# SCH_graduation_atmega_2023-07-09.net
KiCad netlist of a schematic drawn in EasyEDA
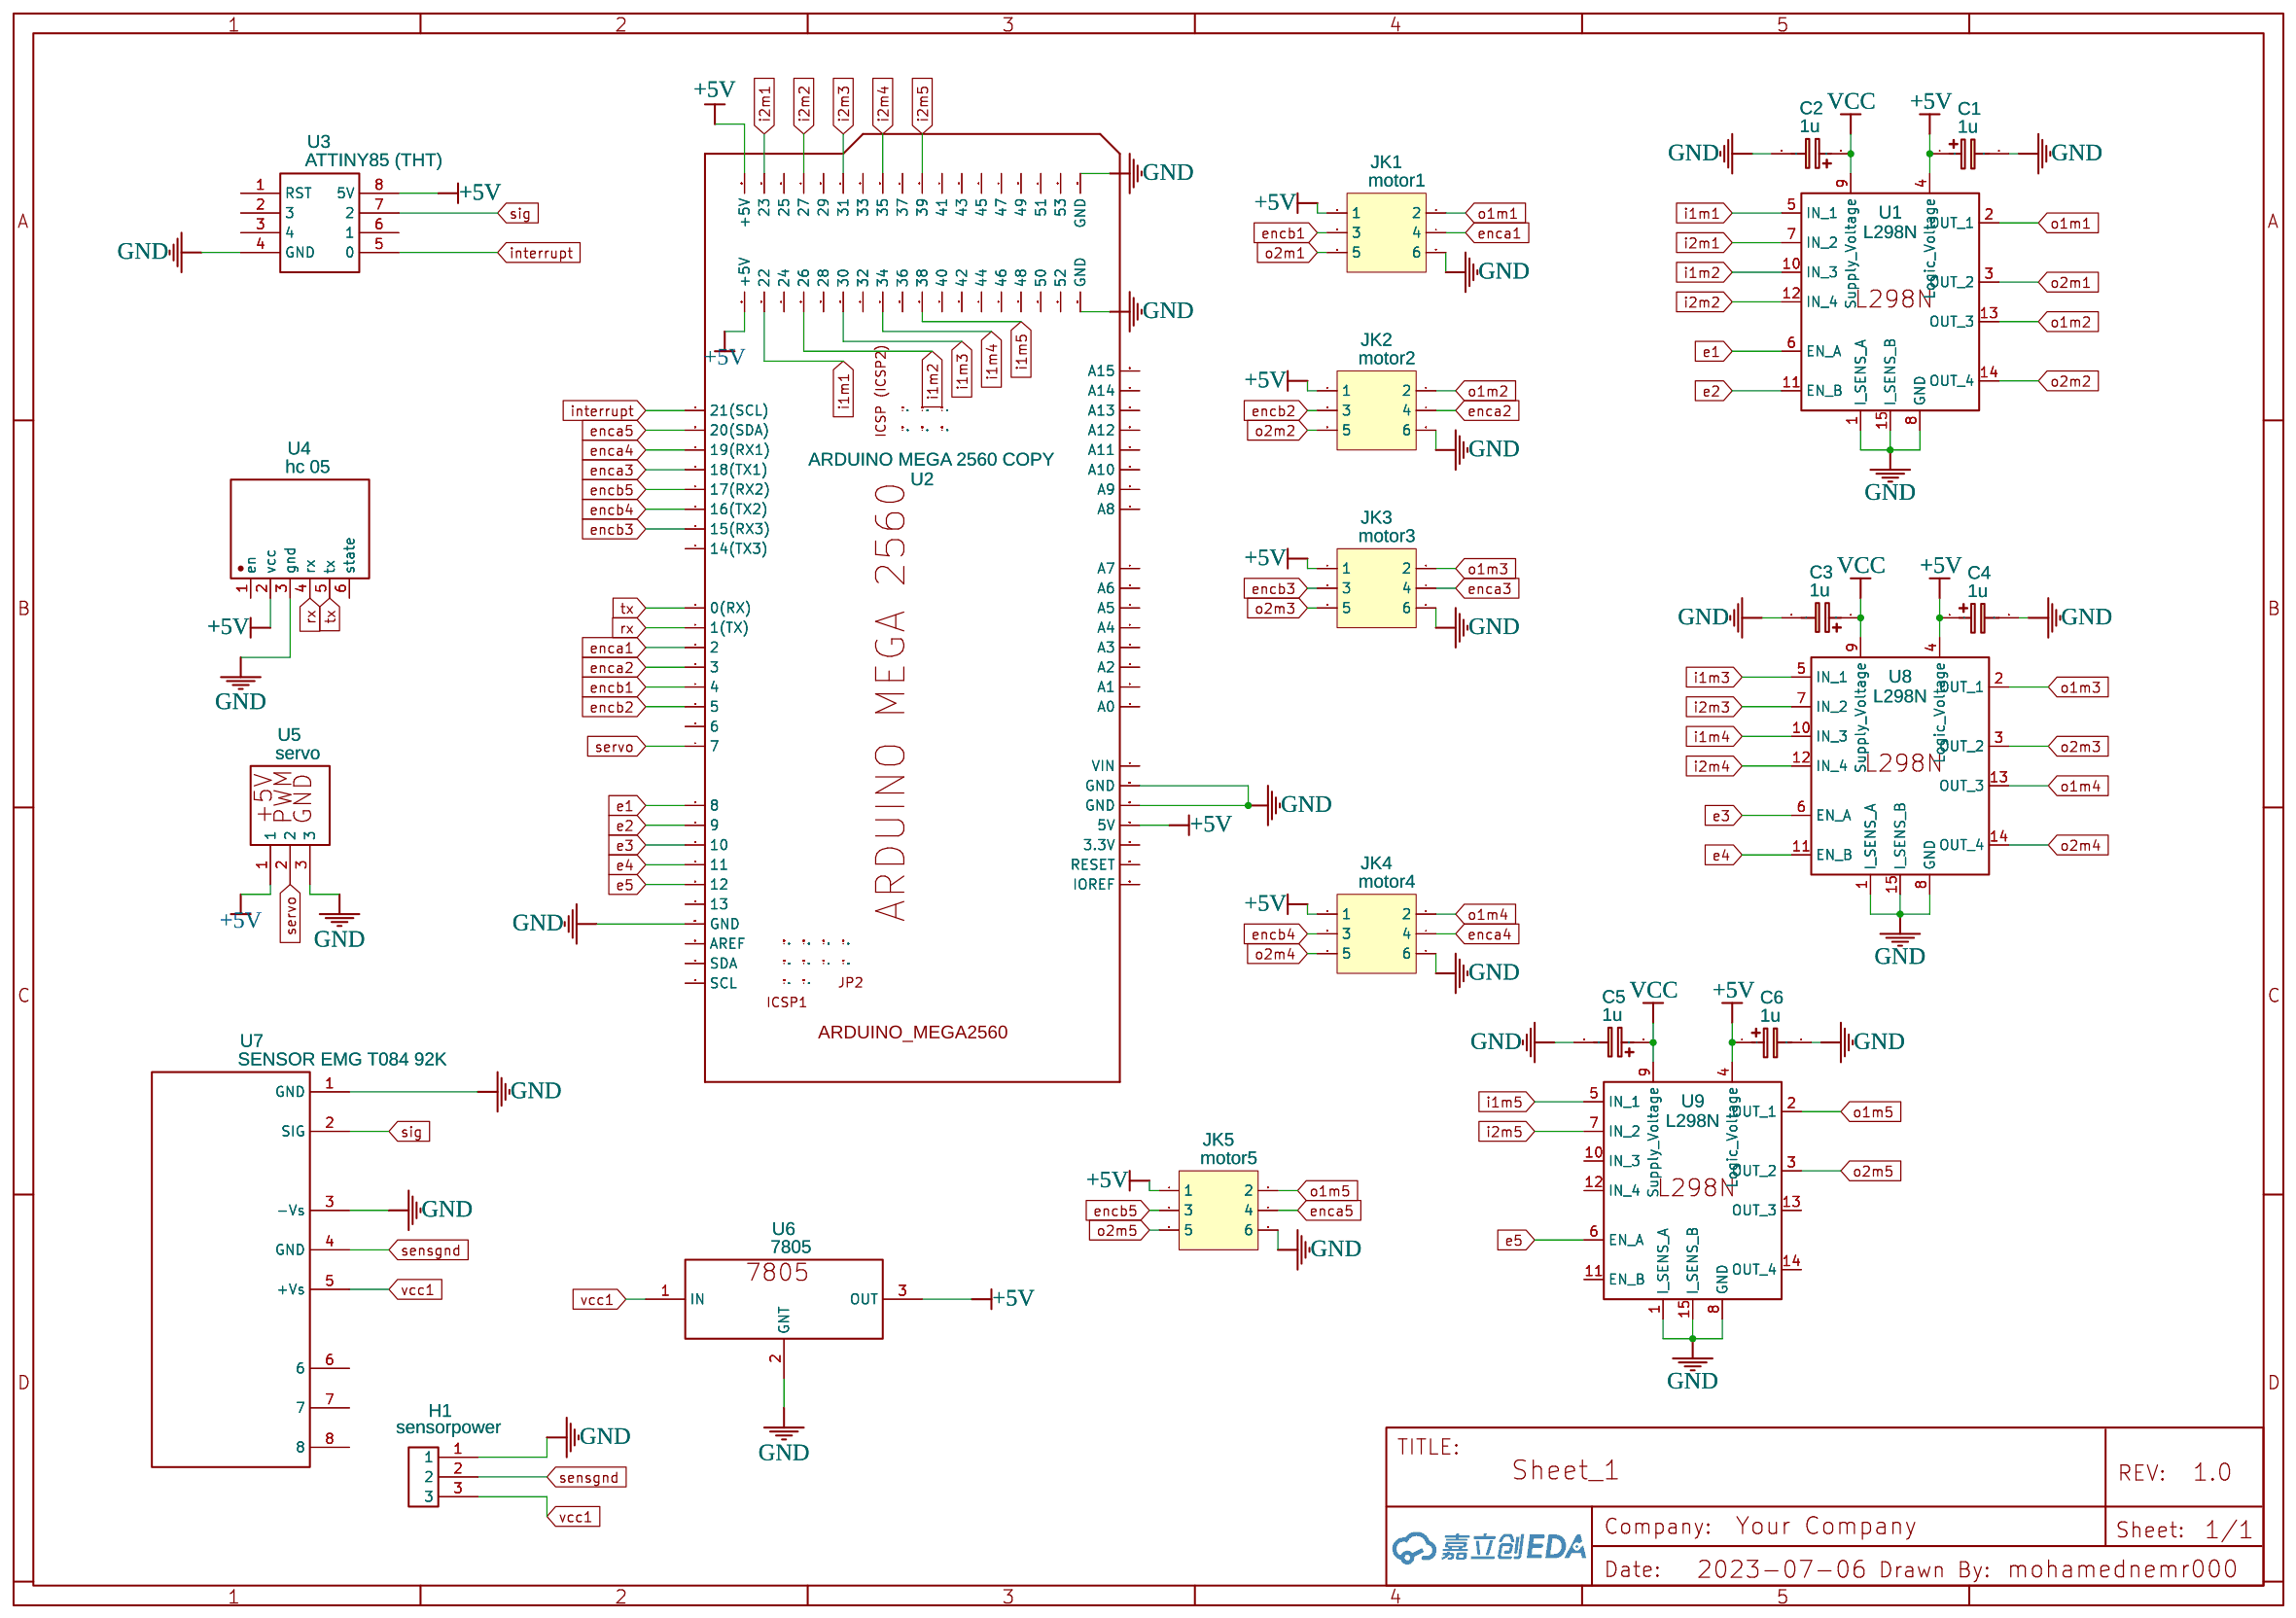
[diagram p0: schematic sheet]

(export (version "E")
  (design (tool "Eeschema 10.0.6"))
  (components
    (comp (ref "C1") (value "1u") (libsource (lib "") (part "CE_TH_D3.0×F1.5_EU_2")))
    (comp (ref "C2") (value "1u") (libsource (lib "") (part "CE_TH_D3.0×F1.5_EU_3")))
    (comp (ref "C3") (value "1u") (libsource (lib "") (part "CE_TH_D3.0×F1.5_EU_1")))
    (comp (ref "C4") (value "1u") (libsource (lib "") (part "CE_TH_D3.0×F1.5_EU")))
    (comp (ref "C5") (value "1u") (libsource (lib "") (part "CE_TH_D3.0×F1.5_EU_1")))
    (comp (ref "C6") (value "1u") (libsource (lib "") (part "CE_TH_D3.0×F1.5_EU")))
    (comp (ref "H1") (value "sensorpower") (libsource (lib "") (part "Header_3*1")))
    (comp (ref "JK1") (value "motor1") (libsource (lib "") (part "CON3*2")))
    (comp (ref "JK2") (value "motor2") (libsource (lib "") (part "CON3*2")))
    (comp (ref "JK3") (value "motor3") (libsource (lib "") (part "CON3*2")))
    (comp (ref "JK4") (value "motor4") (libsource (lib "") (part "CON3*2")))
    (comp (ref "JK5") (value "motor5") (libsource (lib "") (part "CON3*2")))
    (comp (ref "U1") (value "L298N") (libsource (lib "") (part "L298N")))
    (comp (ref "U2") (value "ARDUINO MEGA 2560 COPY") (libsource (lib "") (part "ARDUINO MEGA 2560 COPY")))
    (comp (ref "U3")
      (value "ATTINY85 (THT)")
      (fields
        (field (name "BOM_Manufacturer Part") "ATTINY85-20PU")
        (field (name "BOM_Supplier Part") "1455162")
      )
      (libsource (lib "") (part "ATTINY85 (THT)"))
    )
    (comp (ref "U4") (value "hc 05") (libsource (lib "") (part "hc 05")))
    (comp (ref "U5") (value "servo") (libsource (lib "") (part "servo")))
    (comp (ref "U6") (value "7805") (libsource (lib "") (part "7805")))
    (comp (ref "U7") (value "SENSOR EMG T084 92K") (libsource (lib "") (part "SENSOR EMG T084 92K")))
    (comp (ref "U8") (value "L298N") (libsource (lib "") (part "L298N")))
    (comp (ref "U9") (value "L298N") (libsource (lib "") (part "L298N")))
  )
  (nets
    (net (code "1") (name "+5V") (class "Default")
      (node (ref "C1") (pin "1") (pinfunction "1_1") (pintype "unspecified"))
      (node (ref "C4") (pin "1") (pinfunction "1_1") (pintype "unspecified"))
      (node (ref "C6") (pin "1") (pinfunction "1_1") (pintype "unspecified"))
      (node (ref "JK1") (pin "1") (pinfunction "1_1") (pintype "unspecified"))
      (node (ref "JK2") (pin "1") (pinfunction "1_1") (pintype "unspecified"))
      (node (ref "JK3") (pin "1") (pinfunction "1_1") (pintype "unspecified"))
      (node (ref "JK4") (pin "1") (pinfunction "1_1") (pintype "unspecified"))
      (node (ref "JK5") (pin "1") (pinfunction "1_1") (pintype "unspecified"))
      (node (ref "U1") (pin "4") (pinfunction "Logic_Voltage_4") (pintype "unspecified"))
      (node (ref "U2") (pin "5V_1") (pinfunction "+5V_5V_1") (pintype "unspecified"))
      (node (ref "U2") (pin "5V_2") (pinfunction "+5V_5V_2") (pintype "unspecified"))
      (node (ref "U2") (pin "5V_3") (pinfunction "5V_5V_3") (pintype "unspecified"))
      (node (ref "U3") (pin "8") (pinfunction "5V_8") (pintype "unspecified"))
      (node (ref "U4") (pin "2") (pinfunction "vcc_2") (pintype "unspecified"))
      (node (ref "U5") (pin "1") (pinfunction "1_1") (pintype "unspecified"))
      (node (ref "U6") (pin "3") (pinfunction "OUT_3") (pintype "unspecified"))
      (node (ref "U8") (pin "4") (pinfunction "Logic_Voltage_4") (pintype "unspecified"))
      (node (ref "U9") (pin "4") (pinfunction "Logic_Voltage_4") (pintype "unspecified"))
    )
    (net (code "2") (name "GND") (class "Default")
      (node (ref "C1") (pin "2") (pinfunction "2_2") (pintype "unspecified"))
      (node (ref "C2") (pin "2") (pinfunction "2_2") (pintype "unspecified"))
      (node (ref "C3") (pin "2") (pinfunction "2_2") (pintype "unspecified"))
      (node (ref "C4") (pin "2") (pinfunction "2_2") (pintype "unspecified"))
      (node (ref "C5") (pin "2") (pinfunction "2_2") (pintype "unspecified"))
      (node (ref "C6") (pin "2") (pinfunction "2_2") (pintype "unspecified"))
      (node (ref "H1") (pin "1") (pinfunction "1_1") (pintype "unspecified"))
      (node (ref "JK1") (pin "6") (pinfunction "6_6") (pintype "unspecified"))
      (node (ref "JK2") (pin "6") (pinfunction "6_6") (pintype "unspecified"))
      (node (ref "JK3") (pin "6") (pinfunction "6_6") (pintype "unspecified"))
      (node (ref "JK4") (pin "6") (pinfunction "6_6") (pintype "unspecified"))
      (node (ref "JK5") (pin "6") (pinfunction "6_6") (pintype "unspecified"))
      (node (ref "U1") (pin "1") (pinfunction "I_SENS_A_1") (pintype "unspecified"))
      (node (ref "U1") (pin "15") (pinfunction "I_SENS_B_15") (pintype "unspecified"))
      (node (ref "U1") (pin "8") (pinfunction "GND_8") (pintype "unspecified"))
      (node (ref "U2") (pin "GND_1") (pinfunction "GND_GND_1") (pintype "unspecified"))
      (node (ref "U2") (pin "GND_2") (pinfunction "GND_GND_2") (pintype "unspecified"))
      (node (ref "U2") (pin "GND_3") (pinfunction "GND_GND_3") (pintype "unspecified"))
      (node (ref "U2") (pin "GND_4") (pinfunction "GND_GND_4") (pintype "unspecified"))
      (node (ref "U2") (pin "GND_5") (pinfunction "GND_GND_5") (pintype "unspecified"))
      (node (ref "U3") (pin "4") (pinfunction "GND_4") (pintype "unspecified"))
      (node (ref "U4") (pin "3") (pinfunction "gnd_3") (pintype "unspecified"))
      (node (ref "U5") (pin "3") (pinfunction "3_3") (pintype "unspecified"))
      (node (ref "U6") (pin "2") (pinfunction "GNT_2") (pintype "unspecified"))
      (node (ref "U7") (pin "1") (pinfunction "GND_1") (pintype "unspecified"))
      (node (ref "U7") (pin "3") (pinfunction "-Vs_3") (pintype "unspecified"))
      (node (ref "U8") (pin "1") (pinfunction "I_SENS_A_1") (pintype "unspecified"))
      (node (ref "U8") (pin "15") (pinfunction "I_SENS_B_15") (pintype "unspecified"))
      (node (ref "U8") (pin "8") (pinfunction "GND_8") (pintype "unspecified"))
      (node (ref "U9") (pin "1") (pinfunction "I_SENS_A_1") (pintype "unspecified"))
      (node (ref "U9") (pin "15") (pinfunction "I_SENS_B_15") (pintype "unspecified"))
      (node (ref "U9") (pin "8") (pinfunction "GND_8") (pintype "unspecified"))
    )
    (net (code "3") (name "VCC") (class "Default")
      (node (ref "C2") (pin "1") (pinfunction "1_1") (pintype "unspecified"))
      (node (ref "C3") (pin "1") (pinfunction "1_1") (pintype "unspecified"))
      (node (ref "C5") (pin "1") (pinfunction "1_1") (pintype "unspecified"))
      (node (ref "U1") (pin "9") (pinfunction "Supply_Voltage_9") (pintype "unspecified"))
      (node (ref "U8") (pin "9") (pinfunction "Supply_Voltage_9") (pintype "unspecified"))
      (node (ref "U9") (pin "9") (pinfunction "Supply_Voltage_9") (pintype "unspecified"))
    )
    (net (code "4") (name "e1") (class "Default")
      (node (ref "U1") (pin "6") (pinfunction "EN_A_6") (pintype "unspecified"))
      (node (ref "U2") (pin "8") (pinfunction "8_8") (pintype "unspecified"))
    )
    (net (code "5") (name "e2") (class "Default")
      (node (ref "U1") (pin "11") (pinfunction "EN_B_11") (pintype "unspecified"))
      (node (ref "U2") (pin "9") (pinfunction "9_9") (pintype "unspecified"))
    )
    (net (code "6") (name "e3") (class "Default")
      (node (ref "U2") (pin "10") (pinfunction "10_10") (pintype "unspecified"))
      (node (ref "U8") (pin "6") (pinfunction "EN_A_6") (pintype "unspecified"))
    )
    (net (code "7") (name "e4") (class "Default")
      (node (ref "U2") (pin "11") (pinfunction "11_11") (pintype "unspecified"))
      (node (ref "U8") (pin "11") (pinfunction "EN_B_11") (pintype "unspecified"))
    )
    (net (code "8") (name "e5") (class "Default")
      (node (ref "U2") (pin "12") (pinfunction "12_12") (pintype "unspecified"))
      (node (ref "U9") (pin "6") (pinfunction "EN_A_6") (pintype "unspecified"))
    )
    (net (code "9") (name "enca1") (class "Default")
      (node (ref "JK1") (pin "4") (pinfunction "4_4") (pintype "unspecified"))
      (node (ref "U2") (pin "2") (pinfunction "2_2") (pintype "unspecified"))
    )
    (net (code "10") (name "enca2") (class "Default")
      (node (ref "JK2") (pin "4") (pinfunction "4_4") (pintype "unspecified"))
      (node (ref "U2") (pin "3") (pinfunction "3_3") (pintype "unspecified"))
    )
    (net (code "11") (name "enca3") (class "Default")
      (node (ref "JK3") (pin "4") (pinfunction "4_4") (pintype "unspecified"))
      (node (ref "U2") (pin "18") (pinfunction "18(TX1)_18") (pintype "unspecified"))
    )
    (net (code "12") (name "enca4") (class "Default")
      (node (ref "JK4") (pin "4") (pinfunction "4_4") (pintype "unspecified"))
      (node (ref "U2") (pin "19") (pinfunction "19(RX1)_19") (pintype "unspecified"))
    )
    (net (code "13") (name "enca5") (class "Default")
      (node (ref "JK5") (pin "4") (pinfunction "4_4") (pintype "unspecified"))
      (node (ref "U2") (pin "20") (pinfunction "20(SDA)_20") (pintype "unspecified"))
    )
    (net (code "14") (name "encb1") (class "Default")
      (node (ref "JK1") (pin "3") (pinfunction "3_3") (pintype "unspecified"))
      (node (ref "U2") (pin "4") (pinfunction "4_4") (pintype "unspecified"))
    )
    (net (code "15") (name "encb2") (class "Default")
      (node (ref "JK2") (pin "3") (pinfunction "3_3") (pintype "unspecified"))
      (node (ref "U2") (pin "5") (pinfunction "5_5") (pintype "unspecified"))
    )
    (net (code "16") (name "encb3") (class "Default")
      (node (ref "JK3") (pin "3") (pinfunction "3_3") (pintype "unspecified"))
      (node (ref "U2") (pin "15") (pinfunction "15(RX3)_15") (pintype "unspecified"))
    )
    (net (code "17") (name "encb4") (class "Default")
      (node (ref "JK4") (pin "3") (pinfunction "3_3") (pintype "unspecified"))
      (node (ref "U2") (pin "16") (pinfunction "16(TX2)_16") (pintype "unspecified"))
    )
    (net (code "18") (name "encb5") (class "Default")
      (node (ref "JK5") (pin "3") (pinfunction "3_3") (pintype "unspecified"))
      (node (ref "U2") (pin "17") (pinfunction "17(RX2)_17") (pintype "unspecified"))
    )
    (net (code "19") (name "i1m1") (class "Default")
      (node (ref "U1") (pin "5") (pinfunction "IN_1_5") (pintype "unspecified"))
      (node (ref "U2") (pin "22") (pinfunction "22_22") (pintype "unspecified"))
    )
    (net (code "20") (name "i1m2") (class "Default")
      (node (ref "U1") (pin "10") (pinfunction "IN_3_10") (pintype "unspecified"))
      (node (ref "U2") (pin "26") (pinfunction "26_26") (pintype "unspecified"))
    )
    (net (code "21") (name "i1m3") (class "Default")
      (node (ref "U2") (pin "30") (pinfunction "30_30") (pintype "unspecified"))
      (node (ref "U8") (pin "5") (pinfunction "IN_1_5") (pintype "unspecified"))
    )
    (net (code "22") (name "i1m4") (class "Default")
      (node (ref "U2") (pin "34") (pinfunction "34_34") (pintype "unspecified"))
      (node (ref "U8") (pin "10") (pinfunction "IN_3_10") (pintype "unspecified"))
    )
    (net (code "23") (name "i1m5") (class "Default")
      (node (ref "U2") (pin "38") (pinfunction "38_38") (pintype "unspecified"))
      (node (ref "U9") (pin "5") (pinfunction "IN_1_5") (pintype "unspecified"))
    )
    (net (code "24") (name "i2m1") (class "Default")
      (node (ref "U1") (pin "7") (pinfunction "IN_2_7") (pintype "unspecified"))
      (node (ref "U2") (pin "23") (pinfunction "23_23") (pintype "unspecified"))
    )
    (net (code "25") (name "i2m2") (class "Default")
      (node (ref "U1") (pin "12") (pinfunction "IN_4_12") (pintype "unspecified"))
      (node (ref "U2") (pin "27") (pinfunction "27_27") (pintype "unspecified"))
    )
    (net (code "26") (name "i2m3") (class "Default")
      (node (ref "U2") (pin "31") (pinfunction "31_31") (pintype "unspecified"))
      (node (ref "U8") (pin "7") (pinfunction "IN_2_7") (pintype "unspecified"))
    )
    (net (code "27") (name "i2m4") (class "Default")
      (node (ref "U2") (pin "35") (pinfunction "35_35") (pintype "unspecified"))
      (node (ref "U8") (pin "12") (pinfunction "IN_4_12") (pintype "unspecified"))
    )
    (net (code "28") (name "i2m5") (class "Default")
      (node (ref "U2") (pin "39") (pinfunction "39_39") (pintype "unspecified"))
      (node (ref "U9") (pin "7") (pinfunction "IN_2_7") (pintype "unspecified"))
    )
    (net (code "29") (name "interrupt") (class "Default")
      (node (ref "U2") (pin "21") (pinfunction "21(SCL)_21") (pintype "unspecified"))
      (node (ref "U3") (pin "5") (pinfunction "0_5") (pintype "unspecified"))
    )
    (net (code "30") (name "o1m1") (class "Default")
      (node (ref "JK1") (pin "2") (pinfunction "2_2") (pintype "unspecified"))
      (node (ref "U1") (pin "2") (pinfunction "OUT_1_2") (pintype "unspecified"))
    )
    (net (code "31") (name "o1m2") (class "Default")
      (node (ref "JK2") (pin "2") (pinfunction "2_2") (pintype "unspecified"))
      (node (ref "U1") (pin "13") (pinfunction "OUT_3_13") (pintype "unspecified"))
    )
    (net (code "32") (name "o1m3") (class "Default")
      (node (ref "JK3") (pin "2") (pinfunction "2_2") (pintype "unspecified"))
      (node (ref "U8") (pin "2") (pinfunction "OUT_1_2") (pintype "unspecified"))
    )
    (net (code "33") (name "o1m4") (class "Default")
      (node (ref "JK4") (pin "2") (pinfunction "2_2") (pintype "unspecified"))
      (node (ref "U8") (pin "13") (pinfunction "OUT_3_13") (pintype "unspecified"))
    )
    (net (code "34") (name "o1m5") (class "Default")
      (node (ref "JK5") (pin "2") (pinfunction "2_2") (pintype "unspecified"))
      (node (ref "U9") (pin "2") (pinfunction "OUT_1_2") (pintype "unspecified"))
    )
    (net (code "35") (name "o2m1") (class "Default")
      (node (ref "JK1") (pin "5") (pinfunction "5_5") (pintype "unspecified"))
      (node (ref "U1") (pin "3") (pinfunction "OUT_2_3") (pintype "unspecified"))
    )
    (net (code "36") (name "o2m2") (class "Default")
      (node (ref "JK2") (pin "5") (pinfunction "5_5") (pintype "unspecified"))
      (node (ref "U1") (pin "14") (pinfunction "OUT_4_14") (pintype "unspecified"))
    )
    (net (code "37") (name "o2m3") (class "Default")
      (node (ref "JK3") (pin "5") (pinfunction "5_5") (pintype "unspecified"))
      (node (ref "U8") (pin "3") (pinfunction "OUT_2_3") (pintype "unspecified"))
    )
    (net (code "38") (name "o2m4") (class "Default")
      (node (ref "JK4") (pin "5") (pinfunction "5_5") (pintype "unspecified"))
      (node (ref "U8") (pin "14") (pinfunction "OUT_4_14") (pintype "unspecified"))
    )
    (net (code "39") (name "o2m5") (class "Default")
      (node (ref "JK5") (pin "5") (pinfunction "5_5") (pintype "unspecified"))
      (node (ref "U9") (pin "3") (pinfunction "OUT_2_3") (pintype "unspecified"))
    )
    (net (code "40") (name "rx") (class "Default")
      (node (ref "U2") (pin "1") (pinfunction "1(TX)_1") (pintype "unspecified"))
      (node (ref "U4") (pin "4") (pinfunction "rx_4") (pintype "unspecified"))
    )
    (net (code "41") (name "sensgnd") (class "Default")
      (node (ref "H1") (pin "2") (pinfunction "2_2") (pintype "unspecified"))
      (node (ref "U7") (pin "4") (pinfunction "GND_4") (pintype "unspecified"))
    )
    (net (code "42") (name "servo") (class "Default")
      (node (ref "U2") (pin "7") (pinfunction "7_7") (pintype "unspecified"))
      (node (ref "U5") (pin "2") (pinfunction "2_2") (pintype "unspecified"))
    )
    (net (code "43") (name "sig") (class "Default")
      (node (ref "U3") (pin "7") (pinfunction "2_7") (pintype "unspecified"))
      (node (ref "U7") (pin "2") (pinfunction "SIG_2") (pintype "unspecified"))
    )
    (net (code "44") (name "tx") (class "Default")
      (node (ref "U2") (pin "0") (pinfunction "0(RX)_0") (pintype "unspecified"))
      (node (ref "U4") (pin "5") (pinfunction "tx_5") (pintype "unspecified"))
    )
    (net (code "45") (name "unconnected-(U2-+5V_-PadICSP1_5)") (class "Default")
      (node (ref "U2") (pin "ICSP1_5") (pinfunction "+5V__ICSP1_5") (pintype "unspecified"))
    )
    (net (code "46") (name "unconnected-(U2-+5V_-PadICSP2_2)") (class "Default")
      (node (ref "U2") (pin "ICSP2_2") (pinfunction "+5V__ICSP2_2") (pintype "unspecified"))
    )
    (net (code "47") (name "unconnected-(U2-3.3V-Pad3V3)") (class "Default")
      (node (ref "U2") (pin "3V3") (pinfunction "3.3V_3V3") (pintype "unspecified"))
    )
    (net (code "48") (name "unconnected-(U2-14(TX3)-Pad14)") (class "Default")
      (node (ref "U2") (pin "14") (pinfunction "14(TX3)_14") (pintype "unspecified"))
    )
    (net (code "49") (name "unconnected-(U2-GND_-PadICSP1_1)") (class "Default")
      (node (ref "U2") (pin "ICSP1_1") (pinfunction "GND__ICSP1_1") (pintype "unspecified"))
    )
    (net (code "50") (name "unconnected-(U2-GND_-PadICSP2_6)") (class "Default")
      (node (ref "U2") (pin "ICSP2_6") (pinfunction "GND__ICSP2_6") (pintype "unspecified"))
    )
    (net (code "51") (name "unconnected-(U2-GND_-PadJP2_1)") (class "Default")
      (node (ref "U2") (pin "JP2_1") (pinfunction "GND__JP2_1") (pintype "unspecified"))
    )
    (net (code "52") (name "unconnected-(U2-MISO-PadICSP1_6)") (class "Default")
      (node (ref "U2") (pin "ICSP1_6") (pinfunction "MISO_ICSP1_6") (pintype "unspecified"))
    )
    (net (code "53") (name "unconnected-(U2-MISO-PadICSP2_1)") (class "Default")
      (node (ref "U2") (pin "ICSP2_1") (pinfunction "MISO_ICSP2_1") (pintype "unspecified"))
    )
    (net (code "54") (name "unconnected-(U2-MOSI-PadICSP1_3)") (class "Default")
      (node (ref "U2") (pin "ICSP1_3") (pinfunction "MOSI_ICSP1_3") (pintype "unspecified"))
    )
    (net (code "55") (name "unconnected-(U2-MOSI-PadICSP2_4)") (class "Default")
      (node (ref "U2") (pin "ICSP2_4") (pinfunction "MOSI_ICSP2_4") (pintype "unspecified"))
    )
    (net (code "56") (name "unconnected-(U2-MOSI-PadJP2_3)") (class "Default")
      (node (ref "U2") (pin "JP2_3") (pinfunction "MOSI_JP2_3") (pintype "unspecified"))
    )
    (net (code "57") (name "unconnected-(U2-Pad6)") (class "Default")
      (node (ref "U2") (pin "6") (pinfunction "6_6") (pintype "unspecified"))
    )
    (net (code "58") (name "unconnected-(U2-Pad13)") (class "Default")
      (node (ref "U2") (pin "13") (pinfunction "13_13") (pintype "unspecified"))
    )
    (net (code "59") (name "unconnected-(U2-Pad24)") (class "Default")
      (node (ref "U2") (pin "24") (pinfunction "24_24") (pintype "unspecified"))
    )
    (net (code "60") (name "unconnected-(U2-Pad25)") (class "Default")
      (node (ref "U2") (pin "25") (pinfunction "25_25") (pintype "unspecified"))
    )
    (net (code "61") (name "unconnected-(U2-Pad28)") (class "Default")
      (node (ref "U2") (pin "28") (pinfunction "28_28") (pintype "unspecified"))
    )
    (net (code "62") (name "unconnected-(U2-Pad29)") (class "Default")
      (node (ref "U2") (pin "29") (pinfunction "29_29") (pintype "unspecified"))
    )
    (net (code "63") (name "unconnected-(U2-Pad32)") (class "Default")
      (node (ref "U2") (pin "32") (pinfunction "32_32") (pintype "unspecified"))
    )
    (net (code "64") (name "unconnected-(U2-Pad33)") (class "Default")
      (node (ref "U2") (pin "33") (pinfunction "33_33") (pintype "unspecified"))
    )
    (net (code "65") (name "unconnected-(U2-Pad36)") (class "Default")
      (node (ref "U2") (pin "36") (pinfunction "36_36") (pintype "unspecified"))
    )
    (net (code "66") (name "unconnected-(U2-Pad37)") (class "Default")
      (node (ref "U2") (pin "37") (pinfunction "37_37") (pintype "unspecified"))
    )
    (net (code "67") (name "unconnected-(U2-Pad40)") (class "Default")
      (node (ref "U2") (pin "40") (pinfunction "40_40") (pintype "unspecified"))
    )
    (net (code "68") (name "unconnected-(U2-Pad41)") (class "Default")
      (node (ref "U2") (pin "41") (pinfunction "41_41") (pintype "unspecified"))
    )
    (net (code "69") (name "unconnected-(U2-Pad42)") (class "Default")
      (node (ref "U2") (pin "42") (pinfunction "42_42") (pintype "unspecified"))
    )
    (net (code "70") (name "unconnected-(U2-Pad43)") (class "Default")
      (node (ref "U2") (pin "43") (pinfunction "43_43") (pintype "unspecified"))
    )
    (net (code "71") (name "unconnected-(U2-Pad44)") (class "Default")
      (node (ref "U2") (pin "44") (pinfunction "44_44") (pintype "unspecified"))
    )
    (net (code "72") (name "unconnected-(U2-Pad45)") (class "Default")
      (node (ref "U2") (pin "45") (pinfunction "45_45") (pintype "unspecified"))
    )
    (net (code "73") (name "unconnected-(U2-Pad46)") (class "Default")
      (node (ref "U2") (pin "46") (pinfunction "46_46") (pintype "unspecified"))
    )
    (net (code "74") (name "unconnected-(U2-Pad47)") (class "Default")
      (node (ref "U2") (pin "47") (pinfunction "47_47") (pintype "unspecified"))
    )
    (net (code "75") (name "unconnected-(U2-Pad48)") (class "Default")
      (node (ref "U2") (pin "48") (pinfunction "48_48") (pintype "unspecified"))
    )
    (net (code "76") (name "unconnected-(U2-Pad49)") (class "Default")
      (node (ref "U2") (pin "49") (pinfunction "49_49") (pintype "unspecified"))
    )
    (net (code "77") (name "unconnected-(U2-Pad50)") (class "Default")
      (node (ref "U2") (pin "50") (pinfunction "50_50") (pintype "unspecified"))
    )
    (net (code "78") (name "unconnected-(U2-Pad51)") (class "Default")
      (node (ref "U2") (pin "51") (pinfunction "51_51") (pintype "unspecified"))
    )
    (net (code "79") (name "unconnected-(U2-Pad52)") (class "Default")
      (node (ref "U2") (pin "52") (pinfunction "52_52") (pintype "unspecified"))
    )
    (net (code "80") (name "unconnected-(U2-Pad53)") (class "Default")
      (node (ref "U2") (pin "53") (pinfunction "53_53") (pintype "unspecified"))
    )
    (net (code "81") (name "unconnected-(U2-PadA0)") (class "Default")
      (node (ref "U2") (pin "A0") (pinfunction "A0_A0") (pintype "unspecified"))
    )
    (net (code "82") (name "unconnected-(U2-PadA1)") (class "Default")
      (node (ref "U2") (pin "A1") (pinfunction "A1_A1") (pintype "unspecified"))
    )
    (net (code "83") (name "unconnected-(U2-PadA2)") (class "Default")
      (node (ref "U2") (pin "A2") (pinfunction "A2_A2") (pintype "unspecified"))
    )
    (net (code "84") (name "unconnected-(U2-PadA3)") (class "Default")
      (node (ref "U2") (pin "A3") (pinfunction "A3_A3") (pintype "unspecified"))
    )
    (net (code "85") (name "unconnected-(U2-PadA4)") (class "Default")
      (node (ref "U2") (pin "A4") (pinfunction "A4_A4") (pintype "unspecified"))
    )
    (net (code "86") (name "unconnected-(U2-PadA5)") (class "Default")
      (node (ref "U2") (pin "A5") (pinfunction "A5_A5") (pintype "unspecified"))
    )
    (net (code "87") (name "unconnected-(U2-PadA6)") (class "Default")
      (node (ref "U2") (pin "A6") (pinfunction "A6_A6") (pintype "unspecified"))
    )
    (net (code "88") (name "unconnected-(U2-PadA7)") (class "Default")
      (node (ref "U2") (pin "A7") (pinfunction "A7_A7") (pintype "unspecified"))
    )
    (net (code "89") (name "unconnected-(U2-PadA8)") (class "Default")
      (node (ref "U2") (pin "A8") (pinfunction "A8_A8") (pintype "unspecified"))
    )
    (net (code "90") (name "unconnected-(U2-PadA9)") (class "Default")
      (node (ref "U2") (pin "A9") (pinfunction "A9_A9") (pintype "unspecified"))
    )
    (net (code "91") (name "unconnected-(U2-PadA10)") (class "Default")
      (node (ref "U2") (pin "A10") (pinfunction "A10_A10") (pintype "unspecified"))
    )
    (net (code "92") (name "unconnected-(U2-PadA11)") (class "Default")
      (node (ref "U2") (pin "A11") (pinfunction "A11_A11") (pintype "unspecified"))
    )
    (net (code "93") (name "unconnected-(U2-PadA12)") (class "Default")
      (node (ref "U2") (pin "A12") (pinfunction "A12_A12") (pintype "unspecified"))
    )
    (net (code "94") (name "unconnected-(U2-PadA13)") (class "Default")
      (node (ref "U2") (pin "A13") (pinfunction "A13_A13") (pintype "unspecified"))
    )
    (net (code "95") (name "unconnected-(U2-PadA14)") (class "Default")
      (node (ref "U2") (pin "A14") (pinfunction "A14_A14") (pintype "unspecified"))
    )
    (net (code "96") (name "unconnected-(U2-PadA15)") (class "Default")
      (node (ref "U2") (pin "A15") (pinfunction "A15_A15") (pintype "unspecified"))
    )
    (net (code "97") (name "unconnected-(U2-PadAREF)") (class "Default")
      (node (ref "U2") (pin "AREF") (pinfunction "AREF_AREF") (pintype "unspecified"))
    )
    (net (code "98") (name "unconnected-(U2-PadIOREF)") (class "Default")
      (node (ref "U2") (pin "IOREF") (pinfunction "IOREF_IOREF") (pintype "unspecified"))
    )
    (net (code "99") (name "unconnected-(U2-PadRESET)") (class "Default")
      (node (ref "U2") (pin "RESET") (pinfunction "RESET_RESET") (pintype "unspecified"))
    )
    (net (code "100") (name "unconnected-(U2-PadSCL)") (class "Default")
      (node (ref "U2") (pin "SCL") (pinfunction "SCL_SCL") (pintype "unspecified"))
    )
    (net (code "101") (name "unconnected-(U2-PadSDA)") (class "Default")
      (node (ref "U2") (pin "SDA") (pinfunction "SDA_SDA") (pintype "unspecified"))
    )
    (net (code "102") (name "unconnected-(U2-PadVIN)") (class "Default")
      (node (ref "U2") (pin "VIN") (pinfunction "VIN_VIN") (pintype "unspecified"))
    )
    (net (code "103") (name "unconnected-(U2-RESET_-PadICSP1_2)") (class "Default")
      (node (ref "U2") (pin "ICSP1_2") (pinfunction "RESET__ICSP1_2") (pintype "unspecified"))
    )
    (net (code "104") (name "unconnected-(U2-RESET_-PadICSP2_5)") (class "Default")
      (node (ref "U2") (pin "ICSP2_5") (pinfunction "RESET__ICSP2_5") (pintype "unspecified"))
    )
    (net (code "105") (name "unconnected-(U2-RESET_-PadJP2_2)") (class "Default")
      (node (ref "U2") (pin "JP2_2") (pinfunction "RESET__JP2_2") (pintype "unspecified"))
    )
    (net (code "106") (name "unconnected-(U2-SCK-PadICSP1_4)") (class "Default")
      (node (ref "U2") (pin "ICSP1_4") (pinfunction "SCK_ICSP1_4") (pintype "unspecified"))
    )
    (net (code "107") (name "unconnected-(U2-SCK-PadICSP2_3)") (class "Default")
      (node (ref "U2") (pin "ICSP2_3") (pinfunction "SCK_ICSP2_3") (pintype "unspecified"))
    )
    (net (code "108") (name "unconnected-(U2-SCK-PadJP2_4)") (class "Default")
      (node (ref "U2") (pin "JP2_4") (pinfunction "SCK_JP2_4") (pintype "unspecified"))
    )
    (net (code "109") (name "unconnected-(U3-1-Pad6)") (class "Default")
      (node (ref "U3") (pin "6") (pinfunction "1_6") (pintype "unspecified"))
    )
    (net (code "110") (name "unconnected-(U3-3-Pad2)") (class "Default")
      (node (ref "U3") (pin "2") (pinfunction "3_2") (pintype "unspecified"))
    )
    (net (code "111") (name "unconnected-(U3-4-Pad3)") (class "Default")
      (node (ref "U3") (pin "3") (pinfunction "4_3") (pintype "unspecified"))
    )
    (net (code "112") (name "unconnected-(U3-RST-Pad1)") (class "Default")
      (node (ref "U3") (pin "1") (pinfunction "RST_1") (pintype "unspecified"))
    )
    (net (code "113") (name "unconnected-(U4-en-Pad1)") (class "Default")
      (node (ref "U4") (pin "1") (pinfunction "en_1") (pintype "unspecified"))
    )
    (net (code "114") (name "unconnected-(U4-state-Pad6)") (class "Default")
      (node (ref "U4") (pin "6") (pinfunction "state_6") (pintype "unspecified"))
    )
    (net (code "115") (name "unconnected-(U7-Pad6)") (class "Default")
      (node (ref "U7") (pin "6") (pinfunction "6_6") (pintype "unspecified"))
    )
    (net (code "116") (name "unconnected-(U7-Pad7)") (class "Default")
      (node (ref "U7") (pin "7") (pinfunction "7_7") (pintype "unspecified"))
    )
    (net (code "117") (name "unconnected-(U7-Pad8)") (class "Default")
      (node (ref "U7") (pin "8") (pinfunction "8_8") (pintype "unspecified"))
    )
    (net (code "118") (name "unconnected-(U9-EN_B-Pad11)") (class "Default")
      (node (ref "U9") (pin "11") (pinfunction "EN_B_11") (pintype "unspecified"))
    )
    (net (code "119") (name "unconnected-(U9-IN_3-Pad10)") (class "Default")
      (node (ref "U9") (pin "10") (pinfunction "IN_3_10") (pintype "unspecified"))
    )
    (net (code "120") (name "unconnected-(U9-IN_4-Pad12)") (class "Default")
      (node (ref "U9") (pin "12") (pinfunction "IN_4_12") (pintype "unspecified"))
    )
    (net (code "121") (name "unconnected-(U9-OUT_3-Pad13)") (class "Default")
      (node (ref "U9") (pin "13") (pinfunction "OUT_3_13") (pintype "unspecified"))
    )
    (net (code "122") (name "unconnected-(U9-OUT_4-Pad14)") (class "Default")
      (node (ref "U9") (pin "14") (pinfunction "OUT_4_14") (pintype "unspecified"))
    )
    (net (code "123") (name "vcc1") (class "Default")
      (node (ref "H1") (pin "3") (pinfunction "3_3") (pintype "unspecified"))
      (node (ref "U6") (pin "1") (pinfunction "IN_1") (pintype "unspecified"))
      (node (ref "U7") (pin "5") (pinfunction "+Vs_5") (pintype "unspecified"))
    )
  )
)
